# shifter-4rgb.net
KiCad netlist of a schematic drawn in EAGLE
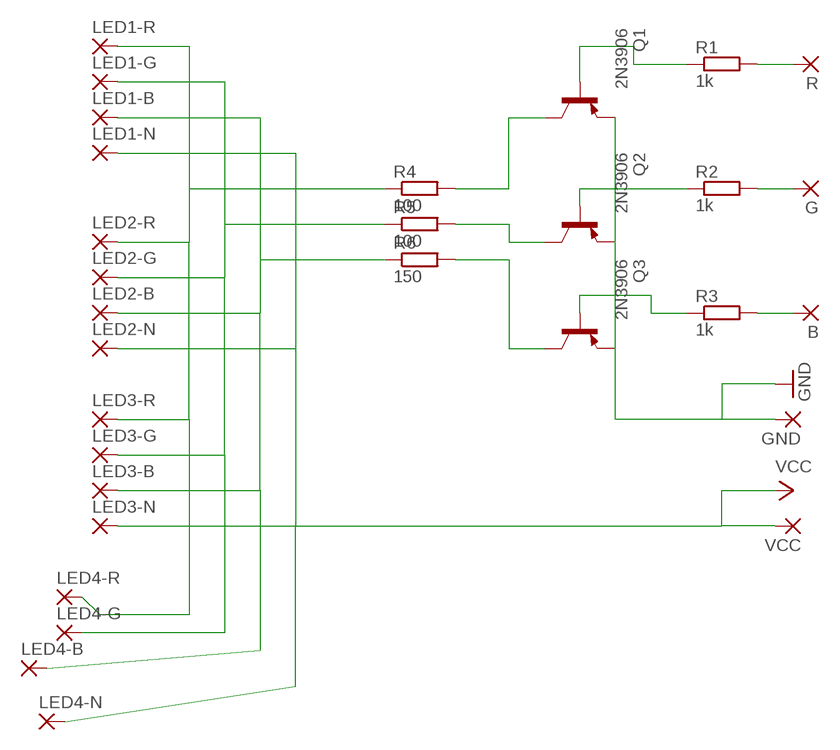
[diagram p0: schematic, sheet 1]

(export (version "E")
  (design (tool "Eeschema 10.0.6"))
  (components
    (comp (ref "B")
      (value "2,54/0,8")
      (footprint "eagle-import:2,54_0,8")
      (libsource (lib "eagle-import") (part "2,54/0,8"))
    )
    (comp (ref "G")
      (value "2,54/0,8")
      (footprint "eagle-import:2,54_0,8")
      (libsource (lib "eagle-import") (part "2,54/0,8"))
    )
    (comp (ref "GND")
      (value "2,54/0,8")
      (footprint "eagle-import:2,54_0,8")
      (libsource (lib "eagle-import") (part "2,54/0,8"))
    )
    (comp (ref "LED1-B")
      (value "2,54/0,8")
      (footprint "eagle-import:2,54_0,8")
      (libsource (lib "eagle-import") (part "2,54/0,8"))
    )
    (comp (ref "LED1-G")
      (value "2,54/0,8")
      (footprint "eagle-import:2,54_0,8")
      (libsource (lib "eagle-import") (part "2,54/0,8"))
    )
    (comp (ref "LED1-N")
      (value "2,54/0,8")
      (footprint "eagle-import:2,54_0,8")
      (libsource (lib "eagle-import") (part "2,54/0,8"))
    )
    (comp (ref "LED1-R")
      (value "2,54/0,8")
      (footprint "eagle-import:2,54_0,8")
      (libsource (lib "eagle-import") (part "2,54/0,8"))
    )
    (comp (ref "LED2-B")
      (value "2,54/0,8")
      (footprint "eagle-import:2,54_0,8")
      (libsource (lib "eagle-import") (part "2,54/0,8"))
    )
    (comp (ref "LED2-G")
      (value "2,54/0,8")
      (footprint "eagle-import:2,54_0,8")
      (libsource (lib "eagle-import") (part "2,54/0,8"))
    )
    (comp (ref "LED2-N")
      (value "2,54/0,8")
      (footprint "eagle-import:2,54_0,8")
      (libsource (lib "eagle-import") (part "2,54/0,8"))
    )
    (comp (ref "LED2-R")
      (value "2,54/0,8")
      (footprint "eagle-import:2,54_0,8")
      (libsource (lib "eagle-import") (part "2,54/0,8"))
    )
    (comp (ref "LED3-B")
      (value "2,54/0,8")
      (footprint "eagle-import:2,54_0,8")
      (libsource (lib "eagle-import") (part "2,54/0,8"))
    )
    (comp (ref "LED3-G")
      (value "2,54/0,8")
      (footprint "eagle-import:2,54_0,8")
      (libsource (lib "eagle-import") (part "2,54/0,8"))
    )
    (comp (ref "LED3-N")
      (value "2,54/0,8")
      (footprint "eagle-import:2,54_0,8")
      (libsource (lib "eagle-import") (part "2,54/0,8"))
    )
    (comp (ref "LED3-R")
      (value "2,54/0,8")
      (footprint "eagle-import:2,54_0,8")
      (libsource (lib "eagle-import") (part "2,54/0,8"))
    )
    (comp (ref "LED4-B")
      (value "2,54/0,8")
      (footprint "eagle-import:2,54_0,8")
      (libsource (lib "eagle-import") (part "2,54/0,8"))
    )
    (comp (ref "LED4-G")
      (value "2,54/0,8")
      (footprint "eagle-import:2,54_0,8")
      (libsource (lib "eagle-import") (part "2,54/0,8"))
    )
    (comp (ref "LED4-N")
      (value "2,54/0,8")
      (footprint "eagle-import:2,54_0,8")
      (libsource (lib "eagle-import") (part "2,54/0,8"))
    )
    (comp (ref "LED4-R")
      (value "2,54/0,8")
      (footprint "eagle-import:2,54_0,8")
      (libsource (lib "eagle-import") (part "2,54/0,8"))
    )
    (comp (ref "Q1")
      (value "2N3906")
      (footprint "eagle-import:TO92")
      (libsource (lib "eagle-import") (part "2N3906"))
    )
    (comp (ref "Q2")
      (value "2N3906")
      (footprint "eagle-import:TO92")
      (libsource (lib "eagle-import") (part "2N3906"))
    )
    (comp (ref "Q3")
      (value "2N3906")
      (footprint "eagle-import:TO92")
      (libsource (lib "eagle-import") (part "2N3906"))
    )
    (comp (ref "R")
      (value "2,54/0,8")
      (footprint "eagle-import:2,54_0,8")
      (libsource (lib "eagle-import") (part "2,54/0,8"))
    )
    (comp (ref "R1")
      (value "1k")
      (footprint "eagle-import:0207_2V")
      (libsource (lib "eagle-import") (part "R-EU_0207/2V"))
    )
    (comp (ref "R2")
      (value "1k")
      (footprint "eagle-import:0207_2V")
      (libsource (lib "eagle-import") (part "R-EU_0207/2V"))
    )
    (comp (ref "R3")
      (value "1k")
      (footprint "eagle-import:0207_2V")
      (libsource (lib "eagle-import") (part "R-EU_0207/2V"))
    )
    (comp (ref "R4")
      (value "100")
      (footprint "eagle-import:0207_2V")
      (libsource (lib "eagle-import") (part "R-EU_0207/2V"))
    )
    (comp (ref "R5")
      (value "100")
      (footprint "eagle-import:0207_7")
      (libsource (lib "eagle-import") (part "R-EU_0207/7"))
    )
    (comp (ref "R6")
      (value "150")
      (footprint "eagle-import:0207_2V")
      (libsource (lib "eagle-import") (part "R-EU_0207/2V"))
    )
    (comp (ref "VCC")
      (value "2,54/0,8")
      (footprint "eagle-import:2,54_0,8")
      (libsource (lib "eagle-import") (part "2,54/0,8"))
    )
  )
  (nets
    (net (code "1") (name "GND") (class "Default")
      (node (ref "GND") (pin "1") (pinfunction "P_1") (pintype "passive"))
      (node (ref "Q1") (pin "3") (pinfunction "E_3") (pintype "passive"))
      (node (ref "Q2") (pin "3") (pinfunction "E_3") (pintype "passive"))
      (node (ref "Q3") (pin "3") (pinfunction "E_3") (pintype "passive"))
    )
    (net (code "2") (name "Net-(B-P)") (class "Default")
      (node (ref "B") (pin "1") (pinfunction "P_1") (pintype "passive"))
      (node (ref "R3") (pin "2") (pinfunction "2_2") (pintype "passive"))
    )
    (net (code "3") (name "Net-(G-P)") (class "Default")
      (node (ref "G") (pin "1") (pinfunction "P_1") (pintype "passive"))
      (node (ref "R2") (pin "2") (pinfunction "2_2") (pintype "passive"))
    )
    (net (code "4") (name "Net-(LED1-B-P)") (class "Default")
      (node (ref "LED1-B") (pin "1") (pinfunction "P_1") (pintype "passive"))
      (node (ref "LED2-B") (pin "1") (pinfunction "P_1") (pintype "passive"))
      (node (ref "LED3-B") (pin "1") (pinfunction "P_1") (pintype "passive"))
      (node (ref "LED4-B") (pin "1") (pinfunction "P_1") (pintype "passive"))
      (node (ref "R6") (pin "1") (pinfunction "1_1") (pintype "passive"))
    )
    (net (code "5") (name "Net-(LED1-G-P)") (class "Default")
      (node (ref "LED1-G") (pin "1") (pinfunction "P_1") (pintype "passive"))
      (node (ref "LED2-G") (pin "1") (pinfunction "P_1") (pintype "passive"))
      (node (ref "LED3-G") (pin "1") (pinfunction "P_1") (pintype "passive"))
      (node (ref "LED4-G") (pin "1") (pinfunction "P_1") (pintype "passive"))
      (node (ref "R5") (pin "1") (pinfunction "1_1") (pintype "passive"))
    )
    (net (code "6") (name "Net-(LED1-R-P)") (class "Default")
      (node (ref "LED1-R") (pin "1") (pinfunction "P_1") (pintype "passive"))
      (node (ref "LED2-R") (pin "1") (pinfunction "P_1") (pintype "passive"))
      (node (ref "LED3-R") (pin "1") (pinfunction "P_1") (pintype "passive"))
      (node (ref "LED4-R") (pin "1") (pinfunction "P_1") (pintype "passive"))
      (node (ref "R4") (pin "1") (pinfunction "1_1") (pintype "passive"))
    )
    (net (code "7") (name "Net-(Q1-B)") (class "Default")
      (node (ref "Q1") (pin "2") (pinfunction "B_2") (pintype "passive"))
      (node (ref "R1") (pin "1") (pinfunction "1_1") (pintype "passive"))
    )
    (net (code "8") (name "Net-(Q1-C)") (class "Default")
      (node (ref "Q1") (pin "1") (pinfunction "C_1") (pintype "passive"))
      (node (ref "R4") (pin "2") (pinfunction "2_2") (pintype "passive"))
    )
    (net (code "9") (name "Net-(Q2-B)") (class "Default")
      (node (ref "Q2") (pin "2") (pinfunction "B_2") (pintype "passive"))
      (node (ref "R2") (pin "1") (pinfunction "1_1") (pintype "passive"))
    )
    (net (code "10") (name "Net-(Q2-C)") (class "Default")
      (node (ref "Q2") (pin "1") (pinfunction "C_1") (pintype "passive"))
      (node (ref "R5") (pin "2") (pinfunction "2_2") (pintype "passive"))
    )
    (net (code "11") (name "Net-(Q3-B)") (class "Default")
      (node (ref "Q3") (pin "2") (pinfunction "B_2") (pintype "passive"))
      (node (ref "R3") (pin "1") (pinfunction "1_1") (pintype "passive"))
    )
    (net (code "12") (name "Net-(Q3-C)") (class "Default")
      (node (ref "Q3") (pin "1") (pinfunction "C_1") (pintype "passive"))
      (node (ref "R6") (pin "2") (pinfunction "2_2") (pintype "passive"))
    )
    (net (code "13") (name "Net-(R-P)") (class "Default")
      (node (ref "R") (pin "1") (pinfunction "P_1") (pintype "passive"))
      (node (ref "R1") (pin "2") (pinfunction "2_2") (pintype "passive"))
    )
    (net (code "14") (name "VCC") (class "Default")
      (node (ref "LED1-N") (pin "1") (pinfunction "P_1") (pintype "passive"))
      (node (ref "LED2-N") (pin "1") (pinfunction "P_1") (pintype "passive"))
      (node (ref "LED3-N") (pin "1") (pinfunction "P_1") (pintype "passive"))
      (node (ref "LED4-N") (pin "1") (pinfunction "P_1") (pintype "passive"))
      (node (ref "VCC") (pin "1") (pinfunction "P_1") (pintype "passive"))
    )
  )
)
